# TouringMachineA2.net
KiCad netlist of a schematic drawn in EAGLE
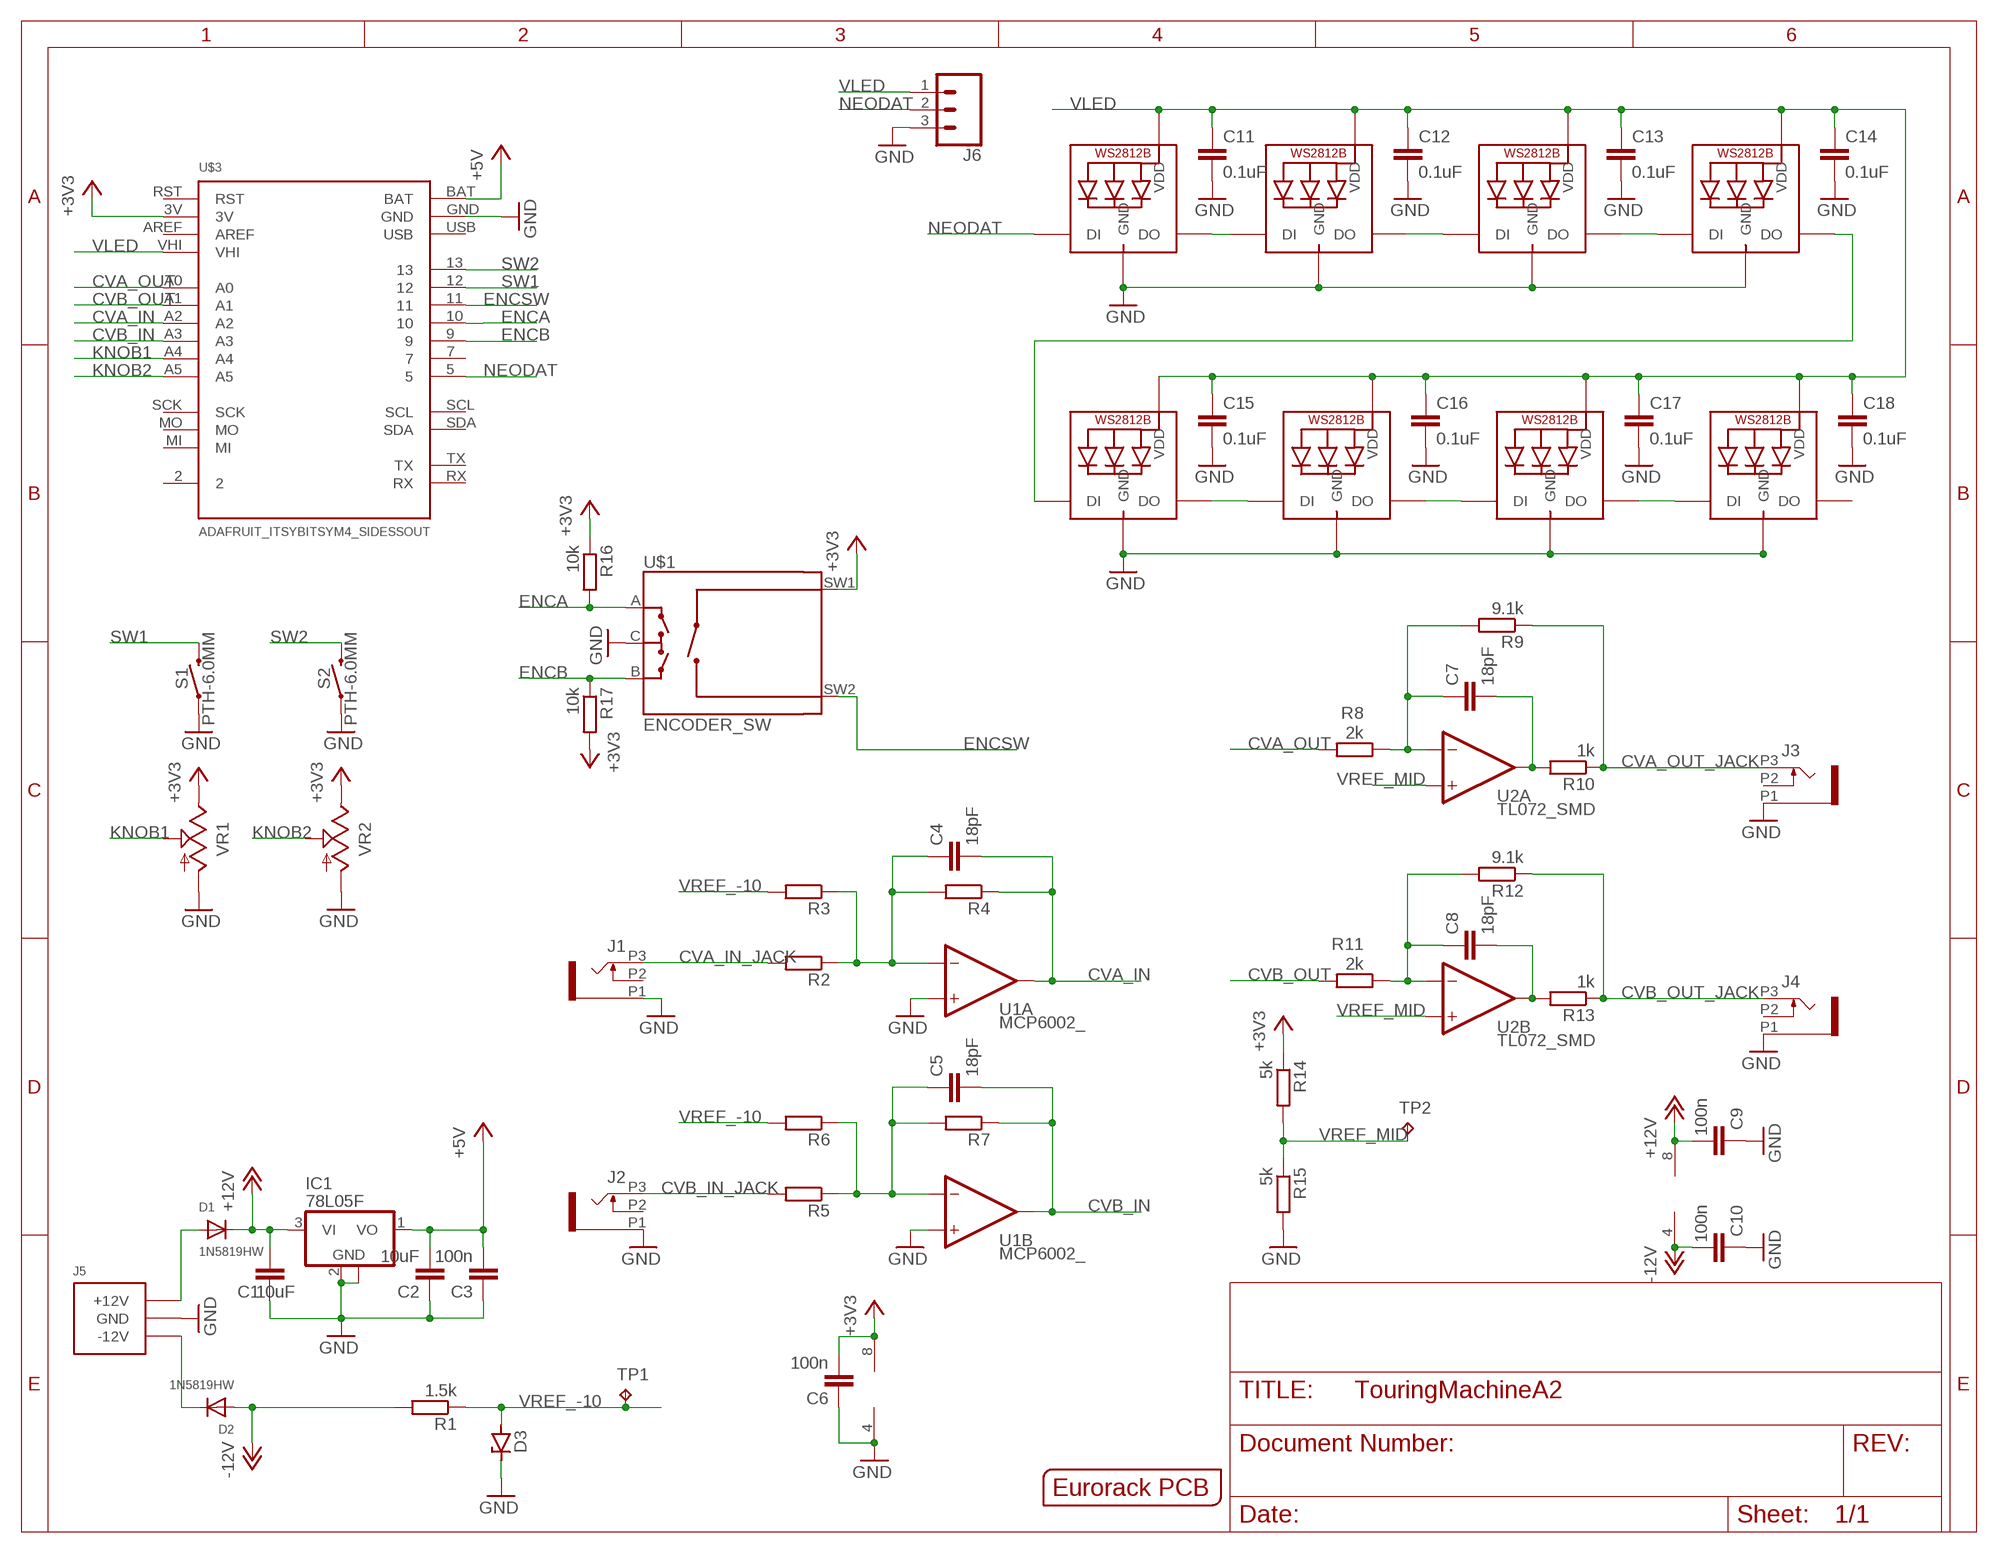
[diagram p0: schematic, sheet 1]

(export (version "E")
  (design (tool "Eeschema 10.0.6"))
  (components
    (comp (ref "C1")
      (value "10uF")
      (footprint "eagle-import:C0603")
      (libsource (lib "eagle-import") (part "C-EUC0603"))
    )
    (comp (ref "C2")
      (value "10uF")
      (footprint "eagle-import:C0603")
      (libsource (lib "eagle-import") (part "C-EUC0603"))
    )
    (comp (ref "C3")
      (value "100n")
      (footprint "eagle-import:C0603")
      (libsource (lib "eagle-import") (part "C-EUC0603"))
    )
    (comp (ref "C4")
      (value "18pF")
      (footprint "eagle-import:C0603")
      (libsource (lib "eagle-import") (part "C-EUC0603"))
    )
    (comp (ref "C5")
      (value "18pF")
      (footprint "eagle-import:C0603")
      (libsource (lib "eagle-import") (part "C-EUC0603"))
    )
    (comp (ref "C6")
      (value "100n")
      (footprint "eagle-import:C0603")
      (libsource (lib "eagle-import") (part "C-EUC0603"))
    )
    (comp (ref "C7")
      (value "18pF")
      (footprint "eagle-import:C0603")
      (libsource (lib "eagle-import") (part "C-EUC0603"))
    )
    (comp (ref "C8")
      (value "18pF")
      (footprint "eagle-import:C0603")
      (libsource (lib "eagle-import") (part "C-EUC0603"))
    )
    (comp (ref "C9")
      (value "100n")
      (footprint "eagle-import:C0603")
      (libsource (lib "eagle-import") (part "C-EUC0603"))
    )
    (comp (ref "C10")
      (value "100n")
      (footprint "eagle-import:C0603")
      (libsource (lib "eagle-import") (part "C-EUC0603"))
    )
    (comp (ref "C11")
      (value "0.1uF")
      (footprint "eagle-import:C0603")
      (libsource (lib "eagle-import") (part "C-EUC0603"))
    )
    (comp (ref "C12")
      (value "0.1uF")
      (footprint "eagle-import:C0603")
      (libsource (lib "eagle-import") (part "C-EUC0603"))
    )
    (comp (ref "C13")
      (value "0.1uF")
      (footprint "eagle-import:C0603")
      (libsource (lib "eagle-import") (part "C-EUC0603"))
    )
    (comp (ref "C14")
      (value "0.1uF")
      (footprint "eagle-import:C0603")
      (libsource (lib "eagle-import") (part "C-EUC0603"))
    )
    (comp (ref "C15")
      (value "0.1uF")
      (footprint "eagle-import:C0603")
      (libsource (lib "eagle-import") (part "C-EUC0603"))
    )
    (comp (ref "C16")
      (value "0.1uF")
      (footprint "eagle-import:C0603")
      (libsource (lib "eagle-import") (part "C-EUC0603"))
    )
    (comp (ref "C17")
      (value "0.1uF")
      (footprint "eagle-import:C0603")
      (libsource (lib "eagle-import") (part "C-EUC0603"))
    )
    (comp (ref "C18")
      (value "0.1uF")
      (footprint "eagle-import:C0603")
      (libsource (lib "eagle-import") (part "C-EUC0603"))
    )
    (comp (ref "D1")
      (value "1N5819HW")
      (footprint "eagle-import:SOD-123")
      (libsource (lib "eagle-import") (part "DIODESOD-123"))
    )
    (comp (ref "D2")
      (value "1N5819HW")
      (footprint "eagle-import:SOD-123")
      (libsource (lib "eagle-import") (part "DIODESOD-123"))
    )
    (comp (ref "D3")
      (value "ZENER-DIODESOT23")
      (footprint "eagle-import:SOT23")
      (libsource (lib "eagle-import") (part "ZENER-DIODESOT23"))
    )
    (comp (ref "IC1")
      (value "78L05F")
      (footprint "eagle-import:SOT89")
      (libsource (lib "eagle-import") (part "78LF05"))
    )
    (comp (ref "J1")
      (value "PJ301_THONKICONN6")
      (footprint "eagle-import:WQP_PJ_301M6")
      (libsource (lib "eagle-import") (part "PJ301_THONKICONN6"))
    )
    (comp (ref "J2")
      (value "PJ301_THONKICONN6")
      (footprint "eagle-import:WQP_PJ_301M6")
      (libsource (lib "eagle-import") (part "PJ301_THONKICONN6"))
    )
    (comp (ref "J3")
      (value "PJ301_THONKICONN6")
      (footprint "eagle-import:WQP_PJ_301M6")
      (libsource (lib "eagle-import") (part "PJ301_THONKICONN6"))
    )
    (comp (ref "J4")
      (value "PJ301_THONKICONN6")
      (footprint "eagle-import:WQP_PJ_301M6")
      (libsource (lib "eagle-import") (part "PJ301_THONKICONN6"))
    )
    (comp (ref "J5")
      (value "POWER_SIMPLE10-OTHERSIDE")
      (footprint "eagle-import:POWER_10_LABELSOTHERSIDE")
      (libsource (lib "eagle-import") (part "POWER_SIMPLE10-OTHERSIDE"))
    )
    (comp (ref "J6")
      (value "CONN_03")
      (footprint "eagle-import:1X03")
      (libsource (lib "eagle-import") (part "CONN_03"))
    )
    (comp (ref "LED1")
      (value "WS2812B5050")
      (footprint "eagle-import:WS2812B")
      (libsource (lib "eagle-import") (part "WS2812B5050"))
    )
    (comp (ref "LED2")
      (value "WS2812B5050")
      (footprint "eagle-import:WS2812B")
      (libsource (lib "eagle-import") (part "WS2812B5050"))
    )
    (comp (ref "LED3")
      (value "WS2812B5050")
      (footprint "eagle-import:WS2812B")
      (libsource (lib "eagle-import") (part "WS2812B5050"))
    )
    (comp (ref "LED4")
      (value "WS2812B5050")
      (footprint "eagle-import:WS2812B")
      (libsource (lib "eagle-import") (part "WS2812B5050"))
    )
    (comp (ref "LED5")
      (value "WS2812B5050")
      (footprint "eagle-import:WS2812B")
      (libsource (lib "eagle-import") (part "WS2812B5050"))
    )
    (comp (ref "LED6")
      (value "WS2812B5050")
      (footprint "eagle-import:WS2812B")
      (libsource (lib "eagle-import") (part "WS2812B5050"))
    )
    (comp (ref "LED7")
      (value "WS2812B5050")
      (footprint "eagle-import:WS2812B")
      (libsource (lib "eagle-import") (part "WS2812B5050"))
    )
    (comp (ref "LED8")
      (value "WS2812B5050")
      (footprint "eagle-import:WS2812B")
      (libsource (lib "eagle-import") (part "WS2812B5050"))
    )
    (comp (ref "PCB1")
      (value "EURORACK_PCB6HP")
      (footprint "eagle-import:EURORACK6HPPCB")
      (libsource (lib "eagle-import") (part "EURORACK_PCB6HP"))
    )
    (comp (ref "R1")
      (value "1.5k")
      (footprint "eagle-import:R0603")
      (libsource (lib "eagle-import") (part "R-EU_R0603"))
    )
    (comp (ref "R2")
      (value "R-EU_R0603")
      (footprint "eagle-import:R0603")
      (libsource (lib "eagle-import") (part "R-EU_R0603"))
    )
    (comp (ref "R3")
      (value "R-EU_R0603")
      (footprint "eagle-import:R0603")
      (libsource (lib "eagle-import") (part "R-EU_R0603"))
    )
    (comp (ref "R4")
      (value "R-EU_R0603")
      (footprint "eagle-import:R0603")
      (libsource (lib "eagle-import") (part "R-EU_R0603"))
    )
    (comp (ref "R5")
      (value "R-EU_R0603")
      (footprint "eagle-import:R0603")
      (libsource (lib "eagle-import") (part "R-EU_R0603"))
    )
    (comp (ref "R6")
      (value "R-EU_R0603")
      (footprint "eagle-import:R0603")
      (libsource (lib "eagle-import") (part "R-EU_R0603"))
    )
    (comp (ref "R7")
      (value "R-EU_R0603")
      (footprint "eagle-import:R0603")
      (libsource (lib "eagle-import") (part "R-EU_R0603"))
    )
    (comp (ref "R8")
      (value "2k")
      (footprint "eagle-import:R0603")
      (libsource (lib "eagle-import") (part "R-EU_R0603"))
    )
    (comp (ref "R9")
      (value "9.1k")
      (footprint "eagle-import:R0603")
      (libsource (lib "eagle-import") (part "R-EU_R0603"))
    )
    (comp (ref "R10")
      (value "1k")
      (footprint "eagle-import:R0603")
      (libsource (lib "eagle-import") (part "R-EU_R0603"))
    )
    (comp (ref "R11")
      (value "2k")
      (footprint "eagle-import:R0603")
      (libsource (lib "eagle-import") (part "R-EU_R0603"))
    )
    (comp (ref "R12")
      (value "9.1k")
      (footprint "eagle-import:R0603")
      (libsource (lib "eagle-import") (part "R-EU_R0603"))
    )
    (comp (ref "R13")
      (value "1k")
      (footprint "eagle-import:R0603")
      (libsource (lib "eagle-import") (part "R-EU_R0603"))
    )
    (comp (ref "R14")
      (value "5k")
      (footprint "eagle-import:R0603")
      (libsource (lib "eagle-import") (part "R-EU_R0603"))
    )
    (comp (ref "R15")
      (value "5k")
      (footprint "eagle-import:R0603")
      (libsource (lib "eagle-import") (part "R-EU_R0603"))
    )
    (comp (ref "R16")
      (value "10k")
      (footprint "eagle-import:R0603")
      (libsource (lib "eagle-import") (part "R-EU_R0603"))
    )
    (comp (ref "R17")
      (value "10k")
      (footprint "eagle-import:R0603")
      (libsource (lib "eagle-import") (part "R-EU_R0603"))
    )
    (comp (ref "S1")
      (value "PTH-6.0MM")
      (footprint "eagle-import:TACTILE_SWITCH_PTH_6.0MM")
      (libsource (lib "eagle-import") (part "MOMENTARY-SWITCH-SPST-PTH-6.0MM"))
    )
    (comp (ref "S2")
      (value "PTH-6.0MM")
      (footprint "eagle-import:TACTILE_SWITCH_PTH_6.0MM")
      (libsource (lib "eagle-import") (part "MOMENTARY-SWITCH-SPST-PTH-6.0MM"))
    )
    (comp (ref "TP1")
      (value "TPTP15R")
      (footprint "eagle-import:TP15R")
      (libsource (lib "eagle-import") (part "TPTP15R"))
    )
    (comp (ref "TP2")
      (value "TPTP15R")
      (footprint "eagle-import:TP15R")
      (libsource (lib "eagle-import") (part "TPTP15R"))
    )
    (comp (ref "U$1")
      (value "ENCODER_SW")
      (footprint "eagle-import:ENCODER_SW")
      (libsource (lib "eagle-import") (part "ENCODER_SW"))
    )
    (comp (ref "U$3")
      (value "ADAFRUIT_ITSYBITSYM4_SIDESSOUT")
      (footprint "eagle-import:ADAFRUIT_ITSYBITSYM4_SIDESOUT")
      (libsource (lib "eagle-import") (part "ADAFRUIT_ITSYBITSYM4_SIDESSOUT"))
    )
    (comp (ref "U1")
      (value "MCP6002_")
      (footprint "eagle-import:SO08")
      (libsource (lib "eagle-import") (part "MCP6002_"))
    )
    (comp (ref "U2")
      (value "TL072_SMD")
      (footprint "eagle-import:SO08")
      (libsource (lib "eagle-import") (part "TL072_SMD"))
    )
    (comp (ref "VR1")
      (value "9MM_SNAP-IN_POT_")
      (footprint "eagle-import:9MM_SNAP-IN_POT")
      (libsource (lib "eagle-import") (part "9MM_SNAP-IN_POT_"))
    )
    (comp (ref "VR2")
      (value "9MM_SNAP-IN_POT_")
      (footprint "eagle-import:9MM_SNAP-IN_POT")
      (libsource (lib "eagle-import") (part "9MM_SNAP-IN_POT_"))
    )
  )
  (nets
    (net (code "1") (name "+3V3") (class "Default")
      (node (ref "C6") (pin "2") (pinfunction "2_2") (pintype "passive"))
      (node (ref "R14") (pin "1") (pinfunction "1_1") (pintype "passive"))
      (node (ref "R16") (pin "1") (pinfunction "1_1") (pintype "passive"))
      (node (ref "R17") (pin "2") (pinfunction "2_2") (pintype "passive"))
      (node (ref "U$1") (pin "SW1") (pinfunction "SW1_SW1") (pintype "passive"))
      (node (ref "U$3") (pin "3V") (pinfunction "3V_3V") (pintype "bidirectional"))
      (node (ref "U1") (pin "8") (pinfunction "V+_8") (pintype "power_in"))
      (node (ref "VR1") (pin "3") (pinfunction "E_3") (pintype "passive"))
      (node (ref "VR2") (pin "3") (pinfunction "E_3") (pintype "passive"))
    )
    (net (code "2") (name "+5V") (class "Default")
      (node (ref "C2") (pin "2") (pinfunction "2_2") (pintype "passive"))
      (node (ref "C3") (pin "2") (pinfunction "2_2") (pintype "passive"))
      (node (ref "IC1") (pin "1") (pinfunction "VO_1") (pintype "passive"))
      (node (ref "U$3") (pin "BAT") (pinfunction "BAT_BAT") (pintype "bidirectional"))
    )
    (net (code "3") (name "+12V") (class "Default")
      (node (ref "C1") (pin "2") (pinfunction "2_2") (pintype "passive"))
      (node (ref "C9") (pin "2") (pinfunction "2_2") (pintype "passive"))
      (node (ref "D1") (pin "C") (pinfunction "C_C") (pintype "passive"))
      (node (ref "IC1") (pin "3") (pinfunction "VI_3") (pintype "input"))
      (node (ref "U2") (pin "8") (pinfunction "V+_8") (pintype "power_in"))
    )
    (net (code "4") (name "-12V") (class "Default")
      (node (ref "C10") (pin "2") (pinfunction "2_2") (pintype "passive"))
      (node (ref "D2") (pin "A") (pinfunction "A_A") (pintype "passive"))
      (node (ref "R1") (pin "2") (pinfunction "2_2") (pintype "passive"))
      (node (ref "U2") (pin "4") (pinfunction "V-_4") (pintype "power_in"))
    )
    (net (code "5") (name "/CVA_IN") (class "Default")
      (node (ref "C4") (pin "2") (pinfunction "2_2") (pintype "passive"))
      (node (ref "R4") (pin "1") (pinfunction "1_1") (pintype "passive"))
      (node (ref "U$3") (pin "A2") (pinfunction "A2_A2") (pintype "bidirectional"))
      (node (ref "U1") (pin "1") (pinfunction "OUT_1") (pintype "output"))
    )
    (net (code "6") (name "/CVA_IN_JACK") (class "Default")
      (node (ref "J1") (pin "P3") (pinfunction "3_P3") (pintype "passive"))
      (node (ref "R2") (pin "2") (pinfunction "2_2") (pintype "passive"))
    )
    (net (code "7") (name "/CVA_OUT") (class "Default")
      (node (ref "R8") (pin "2") (pinfunction "2_2") (pintype "passive"))
      (node (ref "U$3") (pin "A0") (pinfunction "A0_A0") (pintype "bidirectional"))
    )
    (net (code "8") (name "/CVA_OUT_JACK") (class "Default")
      (node (ref "J3") (pin "P3") (pinfunction "3_P3") (pintype "passive"))
      (node (ref "R10") (pin "1") (pinfunction "1_1") (pintype "passive"))
      (node (ref "R9") (pin "1") (pinfunction "1_1") (pintype "passive"))
    )
    (net (code "9") (name "/CVB_IN") (class "Default")
      (node (ref "C5") (pin "2") (pinfunction "2_2") (pintype "passive"))
      (node (ref "R7") (pin "1") (pinfunction "1_1") (pintype "passive"))
      (node (ref "U$3") (pin "A3") (pinfunction "A3_A3") (pintype "bidirectional"))
      (node (ref "U1") (pin "7") (pinfunction "OUT_7") (pintype "output"))
    )
    (net (code "10") (name "/CVB_IN_JACK") (class "Default")
      (node (ref "J2") (pin "P3") (pinfunction "3_P3") (pintype "passive"))
      (node (ref "R5") (pin "2") (pinfunction "2_2") (pintype "passive"))
    )
    (net (code "11") (name "/CVB_OUT") (class "Default")
      (node (ref "R11") (pin "2") (pinfunction "2_2") (pintype "passive"))
      (node (ref "U$3") (pin "A1") (pinfunction "A1_A1") (pintype "bidirectional"))
    )
    (net (code "12") (name "/CVB_OUT_JACK") (class "Default")
      (node (ref "J4") (pin "P3") (pinfunction "3_P3") (pintype "passive"))
      (node (ref "R12") (pin "1") (pinfunction "1_1") (pintype "passive"))
      (node (ref "R13") (pin "1") (pinfunction "1_1") (pintype "passive"))
    )
    (net (code "13") (name "/ENCA") (class "Default")
      (node (ref "R16") (pin "2") (pinfunction "2_2") (pintype "passive"))
      (node (ref "U$1") (pin "A") (pinfunction "A_A") (pintype "bidirectional"))
      (node (ref "U$3") (pin "10") (pinfunction "10_10") (pintype "bidirectional"))
    )
    (net (code "14") (name "/ENCB") (class "Default")
      (node (ref "R17") (pin "1") (pinfunction "1_1") (pintype "passive"))
      (node (ref "U$1") (pin "B") (pinfunction "B_B") (pintype "bidirectional"))
      (node (ref "U$3") (pin "9") (pinfunction "9_9") (pintype "bidirectional"))
    )
    (net (code "15") (name "/ENCSW") (class "Default")
      (node (ref "U$1") (pin "SW2") (pinfunction "SW2_SW2") (pintype "passive"))
      (node (ref "U$3") (pin "11") (pinfunction "11_11") (pintype "bidirectional"))
    )
    (net (code "16") (name "/KNOB1") (class "Default")
      (node (ref "U$3") (pin "A4") (pinfunction "A4_A4") (pintype "bidirectional"))
      (node (ref "VR1") (pin "2") (pinfunction "S_2") (pintype "passive"))
    )
    (net (code "17") (name "/KNOB2") (class "Default")
      (node (ref "U$3") (pin "A5") (pinfunction "A5_A5") (pintype "bidirectional"))
      (node (ref "VR2") (pin "2") (pinfunction "S_2") (pintype "passive"))
    )
    (net (code "18") (name "/NEODAT") (class "Default")
      (node (ref "J6") (pin "2") (pinfunction "2_2") (pintype "passive"))
      (node (ref "LED1") (pin "4-DIN") (pinfunction "DI_4-DIN") (pintype "input"))
      (node (ref "U$3") (pin "5") (pinfunction "5_5") (pintype "bidirectional"))
    )
    (net (code "19") (name "/SW1") (class "Default")
      (node (ref "S1") (pin "3") (pinfunction "2_3") (pintype "passive"))
      (node (ref "U$3") (pin "12") (pinfunction "12_12") (pintype "bidirectional"))
    )
    (net (code "20") (name "/SW2") (class "Default")
      (node (ref "S2") (pin "3") (pinfunction "2_3") (pintype "passive"))
      (node (ref "U$3") (pin "13") (pinfunction "13_13") (pintype "bidirectional"))
    )
    (net (code "21") (name "/VLED") (class "Default")
      (node (ref "C11") (pin "1") (pinfunction "1_1") (pintype "passive"))
      (node (ref "C12") (pin "1") (pinfunction "1_1") (pintype "passive"))
      (node (ref "C13") (pin "1") (pinfunction "1_1") (pintype "passive"))
      (node (ref "C14") (pin "1") (pinfunction "1_1") (pintype "passive"))
      (node (ref "C15") (pin "1") (pinfunction "1_1") (pintype "passive"))
      (node (ref "C16") (pin "1") (pinfunction "1_1") (pintype "passive"))
      (node (ref "C17") (pin "1") (pinfunction "1_1") (pintype "passive"))
      (node (ref "C18") (pin "1") (pinfunction "1_1") (pintype "passive"))
      (node (ref "J6") (pin "1") (pinfunction "1_1") (pintype "passive"))
      (node (ref "LED1") (pin "1-VDD") (pinfunction "VDD_1-VDD") (pintype "power_in"))
      (node (ref "LED2") (pin "1-VDD") (pinfunction "VDD_1-VDD") (pintype "power_in"))
      (node (ref "LED3") (pin "1-VDD") (pinfunction "VDD_1-VDD") (pintype "power_in"))
      (node (ref "LED4") (pin "1-VDD") (pinfunction "VDD_1-VDD") (pintype "power_in"))
      (node (ref "LED5") (pin "1-VDD") (pinfunction "VDD_1-VDD") (pintype "power_in"))
      (node (ref "LED6") (pin "1-VDD") (pinfunction "VDD_1-VDD") (pintype "power_in"))
      (node (ref "LED7") (pin "1-VDD") (pinfunction "VDD_1-VDD") (pintype "power_in"))
      (node (ref "LED8") (pin "1-VDD") (pinfunction "VDD_1-VDD") (pintype "power_in"))
      (node (ref "U$3") (pin "VHI") (pinfunction "VHI_VHI") (pintype "bidirectional"))
    )
    (net (code "22") (name "/VREF_-10") (class "Default")
      (node (ref "D3") (pin "1") (pinfunction "A_1") (pintype "passive"))
      (node (ref "R1") (pin "1") (pinfunction "1_1") (pintype "passive"))
      (node (ref "R3") (pin "2") (pinfunction "2_2") (pintype "passive"))
      (node (ref "R6") (pin "2") (pinfunction "2_2") (pintype "passive"))
      (node (ref "TP1") (pin "TP") (pinfunction "TP_TP") (pintype "input"))
    )
    (net (code "23") (name "/VREF_MID") (class "Default")
      (node (ref "R14") (pin "2") (pinfunction "2_2") (pintype "passive"))
      (node (ref "R15") (pin "1") (pinfunction "1_1") (pintype "passive"))
      (node (ref "TP2") (pin "TP") (pinfunction "TP_TP") (pintype "input"))
      (node (ref "U2") (pin "3") (pinfunction "+IN_3") (pintype "input"))
      (node (ref "U2") (pin "5") (pinfunction "+IN_5") (pintype "input"))
    )
    (net (code "24") (name "GND") (class "Default")
      (node (ref "C1") (pin "1") (pinfunction "1_1") (pintype "passive"))
      (node (ref "C10") (pin "1") (pinfunction "1_1") (pintype "passive"))
      (node (ref "C11") (pin "2") (pinfunction "2_2") (pintype "passive"))
      (node (ref "C12") (pin "2") (pinfunction "2_2") (pintype "passive"))
      (node (ref "C13") (pin "2") (pinfunction "2_2") (pintype "passive"))
      (node (ref "C14") (pin "2") (pinfunction "2_2") (pintype "passive"))
      (node (ref "C15") (pin "2") (pinfunction "2_2") (pintype "passive"))
      (node (ref "C16") (pin "2") (pinfunction "2_2") (pintype "passive"))
      (node (ref "C17") (pin "2") (pinfunction "2_2") (pintype "passive"))
      (node (ref "C18") (pin "2") (pinfunction "2_2") (pintype "passive"))
      (node (ref "C2") (pin "1") (pinfunction "1_1") (pintype "passive"))
      (node (ref "C3") (pin "1") (pinfunction "1_1") (pintype "passive"))
      (node (ref "C6") (pin "1") (pinfunction "1_1") (pintype "passive"))
      (node (ref "C9") (pin "1") (pinfunction "1_1") (pintype "passive"))
      (node (ref "D3") (pin "3") (pinfunction "C_3") (pintype "passive"))
      (node (ref "IC1") (pin "2") (pinfunction "GND_2") (pintype "passive"))
      (node (ref "IC1") (pin "2@1") (pinfunction "GND_2@1") (pintype "passive"))
      (node (ref "J1") (pin "P1") (pinfunction "1_P1") (pintype "passive"))
      (node (ref "J2") (pin "P1") (pinfunction "1_P1") (pintype "passive"))
      (node (ref "J3") (pin "P1") (pinfunction "1_P1") (pintype "passive"))
      (node (ref "J4") (pin "P1") (pinfunction "1_P1") (pintype "passive"))
      (node (ref "J5") (pin "3") (pinfunction "GND_3") (pintype "bidirectional"))
      (node (ref "J5") (pin "4") (pinfunction "GND_4") (pintype "bidirectional"))
      (node (ref "J5") (pin "5") (pinfunction "GND_5") (pintype "bidirectional"))
      (node (ref "J5") (pin "6") (pinfunction "GND_6") (pintype "bidirectional"))
      (node (ref "J5") (pin "7") (pinfunction "GND_7") (pintype "bidirectional"))
      (node (ref "J5") (pin "8") (pinfunction "GND_8") (pintype "bidirectional"))
      (node (ref "J6") (pin "3") (pinfunction "3_3") (pintype "passive"))
      (node (ref "LED1") (pin "3-GND") (pinfunction "GND_3-GND") (pintype "power_in"))
      (node (ref "LED2") (pin "3-GND") (pinfunction "GND_3-GND") (pintype "power_in"))
      (node (ref "LED3") (pin "3-GND") (pinfunction "GND_3-GND") (pintype "power_in"))
      (node (ref "LED4") (pin "3-GND") (pinfunction "GND_3-GND") (pintype "power_in"))
      (node (ref "LED5") (pin "3-GND") (pinfunction "GND_3-GND") (pintype "power_in"))
      (node (ref "LED6") (pin "3-GND") (pinfunction "GND_3-GND") (pintype "power_in"))
      (node (ref "LED7") (pin "3-GND") (pinfunction "GND_3-GND") (pintype "power_in"))
      (node (ref "LED8") (pin "3-GND") (pinfunction "GND_3-GND") (pintype "power_in"))
      (node (ref "R15") (pin "2") (pinfunction "2_2") (pintype "passive"))
      (node (ref "S1") (pin "1") (pinfunction "1_1") (pintype "passive"))
      (node (ref "S2") (pin "1") (pinfunction "1_1") (pintype "passive"))
      (node (ref "U$1") (pin "C") (pinfunction "C_C") (pintype "bidirectional"))
      (node (ref "U$3") (pin "GND") (pinfunction "GND_GND") (pintype "bidirectional"))
      (node (ref "U1") (pin "3") (pinfunction "+IN_3") (pintype "input"))
      (node (ref "U1") (pin "4") (pinfunction "V-_4") (pintype "power_in"))
      (node (ref "U1") (pin "5") (pinfunction "+IN_5") (pintype "input"))
      (node (ref "VR1") (pin "1") (pinfunction "A_1") (pintype "passive"))
      (node (ref "VR2") (pin "1") (pinfunction "A_1") (pintype "passive"))
    )
    (net (code "25") (name "Net-(D1-PadA)") (class "Default")
      (node (ref "D1") (pin "A") (pinfunction "A_A") (pintype "passive"))
      (node (ref "J5") (pin "10") (pinfunction "+12V_10") (pintype "bidirectional"))
      (node (ref "J5") (pin "9") (pinfunction "+12V_9") (pintype "bidirectional"))
    )
    (net (code "26") (name "Net-(D2-PadC)") (class "Default")
      (node (ref "D2") (pin "C") (pinfunction "C_C") (pintype "passive"))
      (node (ref "J5") (pin "1") (pinfunction "-12V_1") (pintype "bidirectional"))
      (node (ref "J5") (pin "2") (pinfunction "-12V_2") (pintype "bidirectional"))
    )
    (net (code "27") (name "Net-(LED1-DO)") (class "Default")
      (node (ref "LED1") (pin "2-DOUT") (pinfunction "DO_2-DOUT") (pintype "output"))
      (node (ref "LED2") (pin "4-DIN") (pinfunction "DI_4-DIN") (pintype "input"))
    )
    (net (code "28") (name "Net-(LED2-DO)") (class "Default")
      (node (ref "LED2") (pin "2-DOUT") (pinfunction "DO_2-DOUT") (pintype "output"))
      (node (ref "LED3") (pin "4-DIN") (pinfunction "DI_4-DIN") (pintype "input"))
    )
    (net (code "29") (name "Net-(LED3-DO)") (class "Default")
      (node (ref "LED3") (pin "2-DOUT") (pinfunction "DO_2-DOUT") (pintype "output"))
      (node (ref "LED4") (pin "4-DIN") (pinfunction "DI_4-DIN") (pintype "input"))
    )
    (net (code "30") (name "Net-(LED4-DO)") (class "Default")
      (node (ref "LED4") (pin "2-DOUT") (pinfunction "DO_2-DOUT") (pintype "output"))
      (node (ref "LED5") (pin "4-DIN") (pinfunction "DI_4-DIN") (pintype "input"))
    )
    (net (code "31") (name "Net-(LED5-DO)") (class "Default")
      (node (ref "LED5") (pin "2-DOUT") (pinfunction "DO_2-DOUT") (pintype "output"))
      (node (ref "LED6") (pin "4-DIN") (pinfunction "DI_4-DIN") (pintype "input"))
    )
    (net (code "32") (name "Net-(LED6-DO)") (class "Default")
      (node (ref "LED6") (pin "2-DOUT") (pinfunction "DO_2-DOUT") (pintype "output"))
      (node (ref "LED7") (pin "4-DIN") (pinfunction "DI_4-DIN") (pintype "input"))
    )
    (net (code "33") (name "Net-(LED7-DO)") (class "Default")
      (node (ref "LED7") (pin "2-DOUT") (pinfunction "DO_2-DOUT") (pintype "output"))
      (node (ref "LED8") (pin "4-DIN") (pinfunction "DI_4-DIN") (pintype "input"))
    )
    (net (code "34") (name "Net-(U1A--IN)") (class "Default")
      (node (ref "C4") (pin "1") (pinfunction "1_1") (pintype "passive"))
      (node (ref "R2") (pin "1") (pinfunction "1_1") (pintype "passive"))
      (node (ref "R3") (pin "1") (pinfunction "1_1") (pintype "passive"))
      (node (ref "R4") (pin "2") (pinfunction "2_2") (pintype "passive"))
      (node (ref "U1") (pin "2") (pinfunction "-IN_2") (pintype "input"))
    )
    (net (code "35") (name "Net-(U1B--IN)") (class "Default")
      (node (ref "C5") (pin "1") (pinfunction "1_1") (pintype "passive"))
      (node (ref "R5") (pin "1") (pinfunction "1_1") (pintype "passive"))
      (node (ref "R6") (pin "1") (pinfunction "1_1") (pintype "passive"))
      (node (ref "R7") (pin "2") (pinfunction "2_2") (pintype "passive"))
      (node (ref "U1") (pin "6") (pinfunction "-IN_6") (pintype "input"))
    )
    (net (code "36") (name "Net-(U2A--IN)") (class "Default")
      (node (ref "C7") (pin "1") (pinfunction "1_1") (pintype "passive"))
      (node (ref "R8") (pin "1") (pinfunction "1_1") (pintype "passive"))
      (node (ref "R9") (pin "2") (pinfunction "2_2") (pintype "passive"))
      (node (ref "U2") (pin "2") (pinfunction "-IN_2") (pintype "input"))
    )
    (net (code "37") (name "Net-(U2A-OUT)") (class "Default")
      (node (ref "C7") (pin "2") (pinfunction "2_2") (pintype "passive"))
      (node (ref "R10") (pin "2") (pinfunction "2_2") (pintype "passive"))
      (node (ref "U2") (pin "1") (pinfunction "OUT_1") (pintype "output"))
    )
    (net (code "38") (name "Net-(U2B--IN)") (class "Default")
      (node (ref "C8") (pin "1") (pinfunction "1_1") (pintype "passive"))
      (node (ref "R11") (pin "1") (pinfunction "1_1") (pintype "passive"))
      (node (ref "R12") (pin "2") (pinfunction "2_2") (pintype "passive"))
      (node (ref "U2") (pin "6") (pinfunction "-IN_6") (pintype "input"))
    )
    (net (code "39") (name "Net-(U2B-OUT)") (class "Default")
      (node (ref "C8") (pin "2") (pinfunction "2_2") (pintype "passive"))
      (node (ref "R13") (pin "2") (pinfunction "2_2") (pintype "passive"))
      (node (ref "U2") (pin "7") (pinfunction "OUT_7") (pintype "output"))
    )
    (net (code "40") (name "unconnected-(J1-2-PadP2)") (class "Default")
      (node (ref "J1") (pin "P2") (pinfunction "2_P2") (pintype "passive"))
    )
    (net (code "41") (name "unconnected-(J2-2-PadP2)") (class "Default")
      (node (ref "J2") (pin "P2") (pinfunction "2_P2") (pintype "passive"))
    )
    (net (code "42") (name "unconnected-(J3-2-PadP2)") (class "Default")
      (node (ref "J3") (pin "P2") (pinfunction "2_P2") (pintype "passive"))
    )
    (net (code "43") (name "unconnected-(J4-2-PadP2)") (class "Default")
      (node (ref "J4") (pin "P2") (pinfunction "2_P2") (pintype "passive"))
    )
    (net (code "44") (name "unconnected-(LED8-DO-Pad2-DOUT)") (class "Default")
      (node (ref "LED8") (pin "2-DOUT") (pinfunction "DO_2-DOUT") (pintype "output"))
    )
    (net (code "45") (name "unconnected-(U$3-Pad2)") (class "Default")
      (node (ref "U$3") (pin "2") (pinfunction "2_2") (pintype "bidirectional"))
    )
    (net (code "46") (name "unconnected-(U$3-Pad7)") (class "Default")
      (node (ref "U$3") (pin "7") (pinfunction "7_7") (pintype "bidirectional"))
    )
    (net (code "47") (name "unconnected-(U$3-PadAREF)") (class "Default")
      (node (ref "U$3") (pin "AREF") (pinfunction "AREF_AREF") (pintype "bidirectional"))
    )
    (net (code "48") (name "unconnected-(U$3-PadMI)") (class "Default")
      (node (ref "U$3") (pin "MI") (pinfunction "MI_MI") (pintype "bidirectional"))
    )
    (net (code "49") (name "unconnected-(U$3-PadMO)") (class "Default")
      (node (ref "U$3") (pin "MO") (pinfunction "MO_MO") (pintype "bidirectional"))
    )
    (net (code "50") (name "unconnected-(U$3-PadRST)") (class "Default")
      (node (ref "U$3") (pin "RST") (pinfunction "RST_RST") (pintype "bidirectional"))
    )
    (net (code "51") (name "unconnected-(U$3-PadRX)") (class "Default")
      (node (ref "U$3") (pin "RX") (pinfunction "RX_RX") (pintype "bidirectional"))
    )
    (net (code "52") (name "unconnected-(U$3-PadSCK)") (class "Default")
      (node (ref "U$3") (pin "SCK") (pinfunction "SCK_SCK") (pintype "bidirectional"))
    )
    (net (code "53") (name "unconnected-(U$3-PadSCL)") (class "Default")
      (node (ref "U$3") (pin "SCL") (pinfunction "SCL_SCL") (pintype "bidirectional"))
    )
    (net (code "54") (name "unconnected-(U$3-PadSDA)") (class "Default")
      (node (ref "U$3") (pin "SDA") (pinfunction "SDA_SDA") (pintype "bidirectional"))
    )
    (net (code "55") (name "unconnected-(U$3-PadTX)") (class "Default")
      (node (ref "U$3") (pin "TX") (pinfunction "TX_TX") (pintype "bidirectional"))
    )
    (net (code "56") (name "unconnected-(U$3-PadUSB)") (class "Default")
      (node (ref "U$3") (pin "USB") (pinfunction "USB_USB") (pintype "bidirectional"))
    )
  )
)
